# Main.net
KiCad netlist of a schematic drawn in Altium Designer
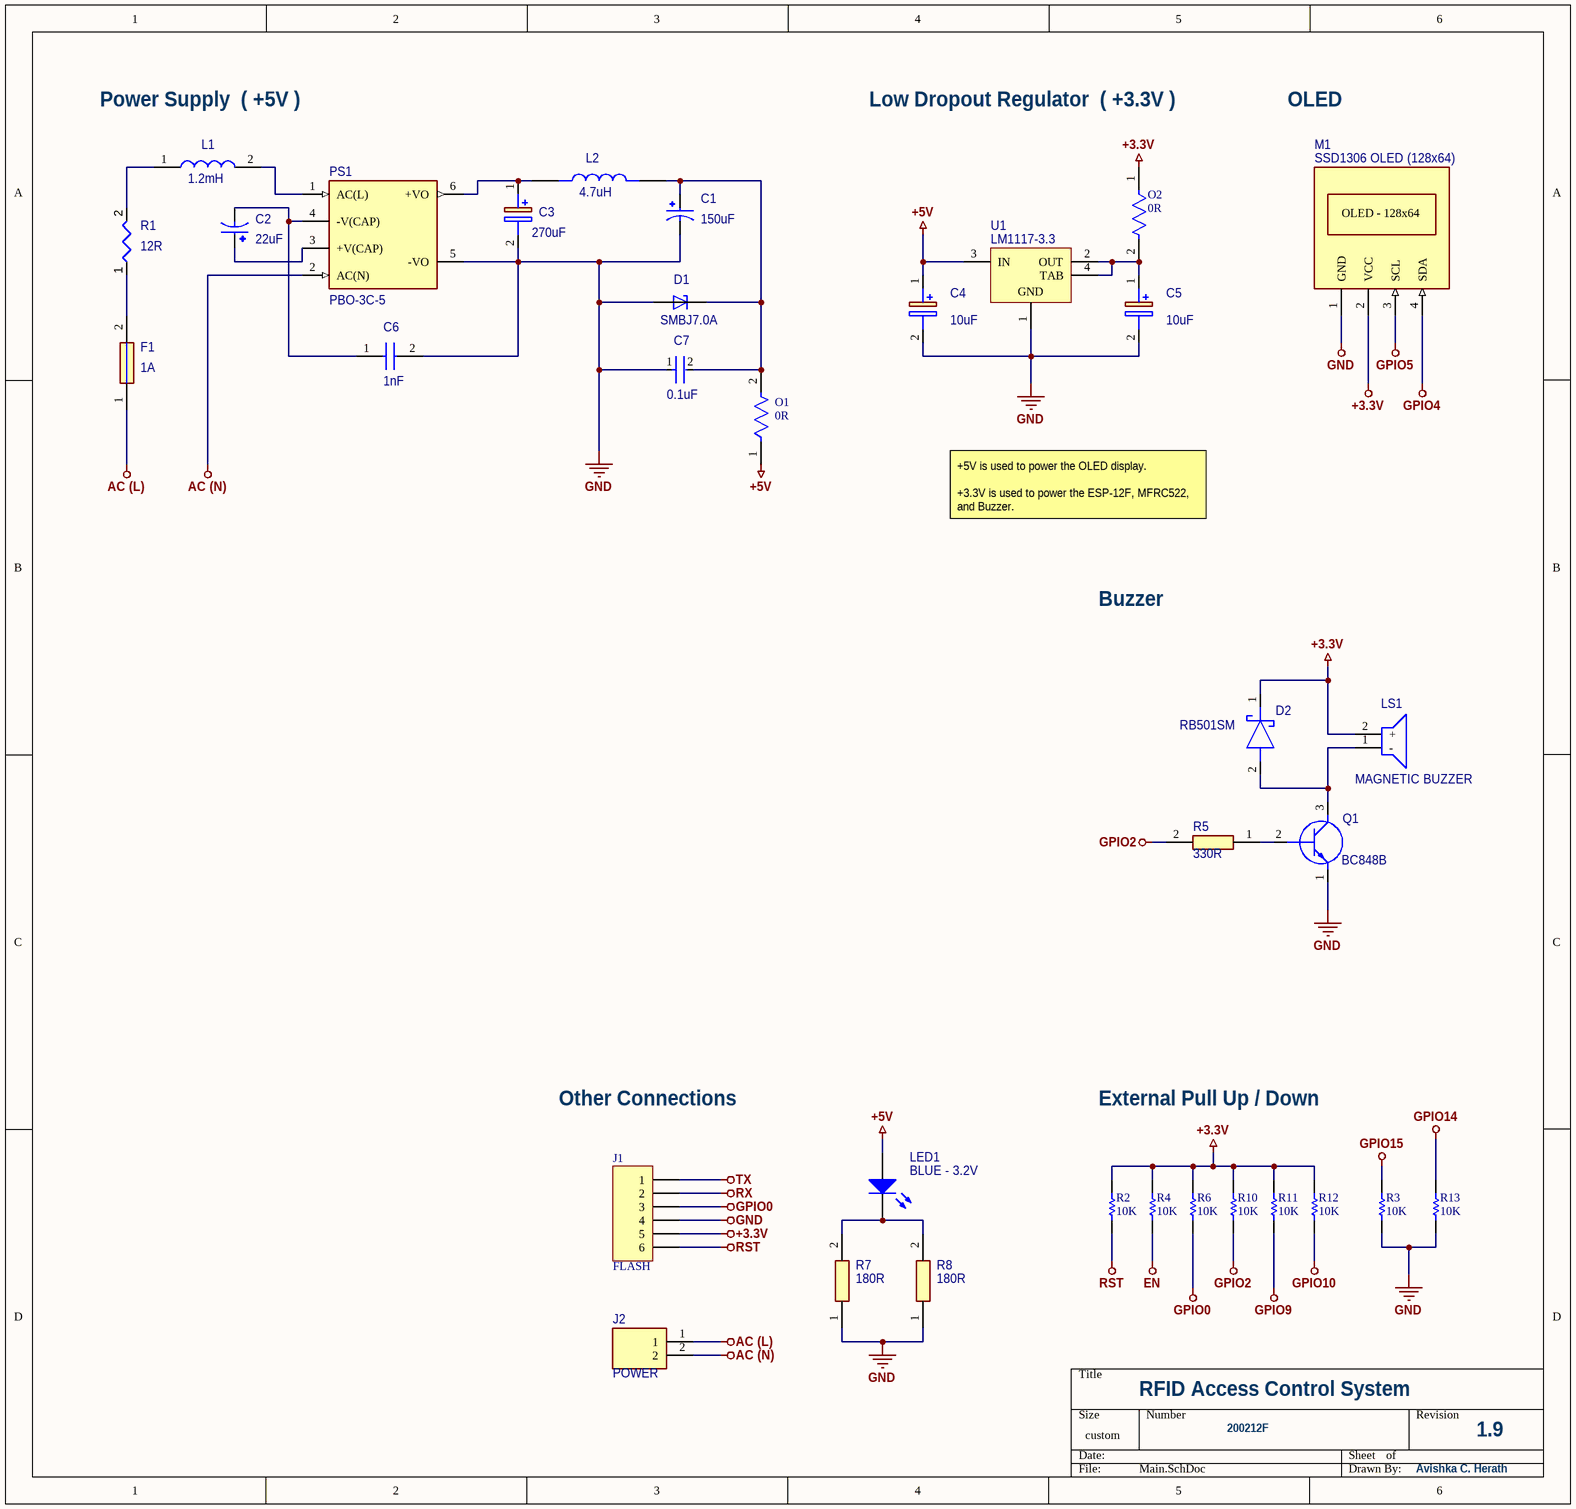
[diagram p0: Main.SchDoc]

(export (version "E")
  (design (tool "Eeschema 10.0.6"))
  (components
    (comp (ref "C1")
      (value "150uF")
      (footprint "CAPPRD500W60D800H1150")
      (description "FR-A")
      (fields (field (name "MF") "{'manufacturer': u'Panasonic'}") (field (name "MP") "UHE1V151MPD1TD"))
      (libsource (lib "SnapEDA_Library") (part "EEUFR1V221B"))
    )
    (comp (ref "C2")
      (value "22uF")
      (footprint "CAPPRD750W80D1600H2500")
      (description "Aluminum Electrolytic Capacitors - Radial Leaded")
      (fields (field (name "MF") "Nichicon") (field (name "MP") "UVR2W220MHD"))
      (libsource (lib "SnapEDA_Library") (part "EEUTP1E272B"))
    )
    (comp (ref "C3")
      (value "270uF")
      (footprint "CAPPRD250W65D630H900")
      (description "Aluminum Organic Polymer Capacitors")
      (fields
        (field (name "MANUFACTURER_PART_NUMBER") "A750EM277M1CAAE015")
        (field (name "MOUSER PART NUMBER") "667-6SEPC560MW+TSS")
      )
      (libsource (lib "SamacSys") (part "6SEPC560MW+TSS"))
    )
    (comp (ref "C4")
      (value "10uF")
      (footprint "SamacSys:T491B")
      (description "Capacitor Polarised")
      (fields
        (field (name "MANUFACTURER_PART_NUMBER") "T491B106M010AT")
        (field (name "MOUSER PART NUMBER") "80-T491B106M010")
      )
      (libsource (lib "*") (part "T491B106M010AT"))
    )
    (comp (ref "C5")
      (value "10uF")
      (footprint "SamacSys:T491B")
      (description "Capacitor Polarised")
      (fields
        (field (name "MANUFACTURER_PART_NUMBER") "T491B106M010AT")
        (field (name "MOUSER PART NUMBER") "80-T491B106M010")
      )
      (libsource (lib "*") (part "T491B106M010AT"))
    )
    (comp (ref "C6")
      (value "1nF")
      (footprint "SamacSys:B32529C8102J")
      (description "Capacitor")
      (fields
        (field (name "MANUFACTURER_PART_NUMBER") "B32529C8102J")
        (field (name "MOUSER PART NUMBER") "871-B32529C8102J")
      )
      (libsource (lib "*") (part "B32529C8102J"))
    )
    (comp (ref "C7")
      (value "0.1uF")
      (footprint "FP-CL10-0_1-MFG")
      (description "CAP CER 0.1UF 50V X7R 0603")
      (fields
        (field (name "MANUFACTURER") "Samsung Electro-Mechanics America, Inc")
        (field (name "MANUFACTURER PART NUMBER") "CL10B104JB8NNNC")
      )
      (libsource (lib "Altium Content Vault") (part "b4654b650e69147ec39a6b967a45e02"))
    )
    (comp (ref "D1")
      (value "SMBJ7.0A")
      (footprint "DIOM4336X265N")
      (fields (field (name "MF") "{'manufacturer': u'Littelfuse'}"))
      (libsource (lib "SnapEDA_Library") (part "SMBJ7.0A"))
    )
    (comp (ref "D2")
      (value "RB501SM")
      (footprint "SamacSys:RB501SM30FHT2R")
      (description "Schottky Diode")
      (fields
        (field (name "MANUFACTURER_PART_NUMBER") "RB501SM-30FHT2R")
        (field (name "MOUSER PART NUMBER") "755-RB501SM-30FHT2R")
      )
      (libsource (lib "*") (part "RB501SM-30FHT2R"))
    )
    (comp (ref "F1")
      (value "1A")
      (footprint "SS5H1AAPH")
      (description "Fuse")
      (fields
        (field (name "MOUSER PART NUMBER") "504-SS-5H-1A-APH")
        (field (name "MANUFACTURER_PART_NUMBER") "SS-5H-1A-APH")
      )
      (libsource (lib "University of Moratuwa") (part "SS-5H-1A-APH"))
    )
    (comp (ref "J1")
      (value "FLASH")
      (footprint "My_1X06")
      (description "Header, 6-Pin")
      (fields (field (name "ASID PART NUMBER") "Header 6-AS"))
      (libsource (lib "Mylib+Rev+4") (part "Header 6"))
    )
    (comp (ref "J2")
      (value "POWER")
      (footprint "SamacSys:TB00250002BE")
      (description "Connector")
      (fields
        (field (name "MANUFACTURER_PART_NUMBER") "TB002-500-02BE")
        (field (name "MOUSER PART NUMBER") "490-TB002-500-02BE")
      )
      (libsource (lib "*") (part "TB002-500-02BE"))
    )
    (comp (ref "L1")
      (value "1.2mH")
      (footprint "SamacSys:RLB9012122KL")
      (description "Inductor")
      (fields
        (field (name "MANUFACTURER_PART_NUMBER") "RLB9012-122KL")
        (field (name "MOUSER PART NUMBER") "652-RLB9012-122KL")
      )
      (libsource (lib "*") (part "RLB9012-122KL"))
    )
    (comp (ref "L2")
      (value "4.7uH")
      (footprint "IND_ASPI-0615FS-4R7M-T2")
      (fields (field (name "MF") "{'manufacturer': u'Abracon'}") (field (name "MP") "ASPI-0615FS-4R7M-T2"))
      (libsource (lib "SnapEDA_Library") (part "ASPI-0615FS-4R7M-T2"))
    )
    (comp (ref "LED1")
      (value "BLUE - 3.2V")
      (footprint "3528")
      (description "SMD mono-color Top LED, WL-SMTW, Blue")
      (fields (field (name "PARTNUMBER") "150141BS73100") (field (name "MANUFACTURER") "Wuerth Elektronik"))
      (libsource (lib "Altium Content Vault") (part "WE-LED_K1A2-2"))
    )
    (comp (ref "LS1")
      (value "MAGNETIC BUZZER")
      (footprint "SamacSys:CMI1295IC0385T")
      (description "Loudspeaker or Buzzer")
      (fields
        (field (name "MANUFACTURER_PART_NUMBER") "CMI-1295IC-0385T")
        (field (name "MOUSER PART NUMBER") "490-CMI-1295IC-0385T")
      )
      (libsource (lib "*") (part "CMI-1295IC-0385T"))
    )
    (comp (ref "M1")
      (value "SSD1306 OLED (128x64)")
      (footprint "SSD1306 OLED (128x64)-Footprint-1")
      (libsource (lib "University of Moratuwa") (part "SSD1306 OLED (128x64)"))
    )
    (comp (ref "O1")
      (value "0R")
      (footprint "FP-RC0805-MFG")
      (description "RES SMD 0 OHM JUMPER 1/8W 0805")
      (fields
        (field (name "OCTOPART") "https://octopart.com/rc0805fr-070rl-yageo-9293404")
        (field (name "MANUFACTURER") "Yageo")
      )
      (libsource (lib "Altium Content Vault") (part "1029c3af85768c4190bb7ad29bc67b5"))
    )
    (comp (ref "O2")
      (value "0R")
      (footprint "FP-RC0805-MFG")
      (description "RES SMD 0 OHM JUMPER 1/8W 0805")
      (fields
        (field (name "OCTOPART") "https://octopart.com/rc0805fr-070rl-yageo-9293404")
        (field (name "MANUFACTURER") "Yageo")
      )
      (libsource (lib "Altium Content Vault") (part "1029c3af85768c4190bb7ad29bc67b5"))
    )
    (comp (ref "PS1")
      (value "PBO-3C-5")
      (footprint "CONV_PBO-3C-5")
      (fields (field (name "MF") "{'manufacturer': u'CUI'}"))
      (libsource (lib "SnapEDA_Library") (part "PBO-3C-5"))
    )
    (comp (ref "Q1")
      (value "BC848B")
      (footprint "SamacSys:SOT95P240X120-3N")
      (description "Transistor BJT NPN")
      (fields
        (field (name "MANUFACTURER_PART_NUMBER") "BC848BHZGT116")
        (field (name "MOUSER PART NUMBER") "755-BC848BHZGT116")
      )
      (libsource (lib "*") (part "BC848BHZGT116"))
    )
    (comp (ref "R1")
      (value "12R")
      (footprint "WA84-12RJI-Footprint-1")
      (libsource (lib "University of Moratuwa") (part "WA84-12RJI"))
    )
    (comp (ref "R2")
      (value "10K")
      (footprint "RESC2013X60X35ML10T20")
      (description "Res Thick Film 0805 10K Ohm 1% 0.125W(1/8W) +/-100ppm/C Epoxy Pad SMD T/R")
      (libsource (lib "University of Moratuwa") (part "RES-2"))
    )
    (comp (ref "R3")
      (value "10K")
      (footprint "RESC2013X60X35ML10T20")
      (description "Res Thick Film 0805 10K Ohm 1% 0.125W(1/8W) +/-100ppm/C Epoxy Pad SMD T/R")
      (libsource (lib "University of Moratuwa") (part "RES-2"))
    )
    (comp (ref "R4")
      (value "10K")
      (footprint "RESC2013X60X35ML10T20")
      (description "Res Thick Film 0805 10K Ohm 1% 0.125W(1/8W) +/-100ppm/C Epoxy Pad SMD T/R")
      (libsource (lib "University of Moratuwa") (part "RES-2"))
    )
    (comp (ref "R5")
      (value "330R")
      (footprint "SamacSys:RESC2012X60N")
      (description "Resistor")
      (fields
        (field (name "MANUFACTURER_PART_NUMBER") "RC0805FR-07330RL")
        (field (name "MOUSER PART NUMBER") "603-RC0805FR-07330RL")
      )
      (libsource (lib "*") (part "RC0805FR-07330RL"))
    )
    (comp (ref "R6")
      (value "10K")
      (footprint "RESC2013X60X35ML10T20")
      (description "Res Thick Film 0805 10K Ohm 1% 0.125W(1/8W) +/-100ppm/C Epoxy Pad SMD T/R")
      (libsource (lib "University of Moratuwa") (part "RES-2"))
    )
    (comp (ref "R7")
      (value "180R")
      (footprint "SamacSys:RESC2012X60N")
      (description "Resistor")
      (fields
        (field (name "MANUFACTURER_PART_NUMBER") "RC0805FR-07180RL")
        (field (name "MOUSER PART NUMBER") "603-RC0805FR-07180RL")
      )
      (libsource (lib "*") (part "RC0805FR-07180RL"))
    )
    (comp (ref "R8")
      (value "180R")
      (footprint "SamacSys:RESC2012X60N")
      (description "Resistor")
      (fields
        (field (name "MANUFACTURER_PART_NUMBER") "RC0805FR-07180RL")
        (field (name "MOUSER PART NUMBER") "603-RC0805FR-07180RL")
      )
      (libsource (lib "*") (part "RC0805FR-07180RL"))
    )
    (comp (ref "R10")
      (value "10K")
      (footprint "RESC2013X60X35ML10T20")
      (description "Res Thick Film 0805 10K Ohm 1% 0.125W(1/8W) +/-100ppm/C Epoxy Pad SMD T/R")
      (libsource (lib "University of Moratuwa") (part "RES-2"))
    )
    (comp (ref "R11")
      (value "10K")
      (footprint "RESC2013X60X35ML10T20")
      (description "Res Thick Film 0805 10K Ohm 1% 0.125W(1/8W) +/-100ppm/C Epoxy Pad SMD T/R")
      (libsource (lib "University of Moratuwa") (part "RES-2"))
    )
    (comp (ref "R12")
      (value "10K")
      (footprint "RESC2013X60X35ML10T20")
      (description "Res Thick Film 0805 10K Ohm 1% 0.125W(1/8W) +/-100ppm/C Epoxy Pad SMD T/R")
      (libsource (lib "University of Moratuwa") (part "RES-2"))
    )
    (comp (ref "R13")
      (value "10K")
      (footprint "RESC2013X60X35ML10T20")
      (description "Res Thick Film 0805 10K Ohm 1% 0.125W(1/8W) +/-100ppm/C Epoxy Pad SMD T/R")
      (libsource (lib "University of Moratuwa") (part "RES-2"))
    )
    (comp (ref "U1")
      (value "LM1117-3.3")
      (footprint "DCY0004A_L")
      (description "800mA Low-Dropout Linear Regulator, 4-pin SOT-223, Pb-Free")
      (fields
        (field (name "PARTNUMBER") "LM1117MPX-3.3/NOPB")
        (field (name "MANUFACTURER") "Texas Instruments")
      )
      (libsource (lib "Altium Content Vault") (part "PM-REG-LM1086-SOT4"))
    )
  )
  (nets
    (net (code "1") (name "+3.3V") (class "Default")
      (node (ref "D2") (pin "1") (pinfunction "K_1") (pintype "passive"))
      (node (ref "J1") (pin "5") (pinfunction "5_5") (pintype "passive"))
      (node (ref "LS1") (pin "2") (pinfunction "+_2") (pintype "passive"))
      (node (ref "M1") (pin "2") (pinfunction "VCC_2") (pintype "power_in"))
      (node (ref "O2") (pin "1") (pinfunction "1_1") (pintype "passive"))
      (node (ref "R10") (pin "2") (pinfunction "2_2") (pintype "passive"))
      (node (ref "R11") (pin "2") (pinfunction "2_2") (pintype "passive"))
      (node (ref "R12") (pin "2") (pinfunction "2_2") (pintype "passive"))
      (node (ref "R2") (pin "1") (pinfunction "1_1") (pintype "passive"))
      (node (ref "R4") (pin "1") (pinfunction "1_1") (pintype "passive"))
      (node (ref "R6") (pin "2") (pinfunction "2_2") (pintype "passive"))
    )
    (net (code "2") (name "+5V") (class "Default")
      (node (ref "C4") (pin "1") (pinfunction "+_1") (pintype "passive"))
      (node (ref "LED1") (pin "2") (pinfunction "A_2") (pintype "passive"))
      (node (ref "O1") (pin "1") (pinfunction "1_1") (pintype "passive"))
      (node (ref "U1") (pin "3") (pinfunction "IN_3") (pintype "power_in"))
    )
    (net (code "3") (name "AC (L)") (class "Default")
      (node (ref "F1") (pin "1") (pinfunction "1_1") (pintype "passive"))
      (node (ref "J2") (pin "1") (pinfunction "1_1") (pintype "passive"))
    )
    (net (code "4") (name "AC (N)") (class "Default")
      (node (ref "J2") (pin "2") (pinfunction "2_2") (pintype "passive"))
      (node (ref "PS1") (pin "2") (pinfunction "AC(N)_2") (pintype "input"))
    )
    (net (code "5") (name "EN") (class "Default")
      (node (ref "R4") (pin "2") (pinfunction "2_2") (pintype "passive"))
    )
    (net (code "6") (name "GND") (class "Default")
      (node (ref "C1") (pin "N") (pinfunction "N_N") (pintype "passive"))
      (node (ref "C3") (pin "2") (pinfunction "-_2") (pintype "passive"))
      (node (ref "C4") (pin "2") (pinfunction "-_2") (pintype "passive"))
      (node (ref "C5") (pin "2") (pinfunction "-_2") (pintype "passive"))
      (node (ref "C6") (pin "2") (pinfunction "2_2") (pintype "passive"))
      (node (ref "C7") (pin "1") (pinfunction "1_1") (pintype "passive"))
      (node (ref "D1") (pin "A") (pinfunction "A_A") (pintype "passive"))
      (node (ref "J1") (pin "4") (pinfunction "4_4") (pintype "passive"))
      (node (ref "M1") (pin "1") (pinfunction "GND_1") (pintype "power_in"))
      (node (ref "PS1") (pin "5") (pinfunction "-VO_5") (pintype "passive"))
      (node (ref "Q1") (pin "1") (pinfunction "E_1") (pintype "passive"))
      (node (ref "R13") (pin "2") (pinfunction "2_2") (pintype "passive"))
      (node (ref "R3") (pin "2") (pinfunction "2_2") (pintype "passive"))
      (node (ref "R7") (pin "1") (pinfunction "1_1") (pintype "passive"))
      (node (ref "R8") (pin "1") (pinfunction "1_1") (pintype "passive"))
      (node (ref "U1") (pin "1") (pinfunction "GND_1") (pintype "power_in"))
    )
    (net (code "7") (name "GPIO0") (class "Default")
      (node (ref "J1") (pin "3") (pinfunction "3_3") (pintype "passive"))
      (node (ref "R6") (pin "1") (pinfunction "1_1") (pintype "passive"))
    )
    (net (code "8") (name "GPIO2") (class "Default")
      (node (ref "R10") (pin "1") (pinfunction "1_1") (pintype "passive"))
      (node (ref "R5") (pin "2") (pinfunction "2_2") (pintype "passive"))
    )
    (net (code "9") (name "GPIO4") (class "Default")
      (node (ref "M1") (pin "4") (pinfunction "SDA_4") (pintype "input"))
    )
    (net (code "10") (name "GPIO5") (class "Default")
      (node (ref "M1") (pin "3") (pinfunction "SCL_3") (pintype "input"))
    )
    (net (code "11") (name "GPIO9") (class "Default")
      (node (ref "R11") (pin "1") (pinfunction "1_1") (pintype "passive"))
    )
    (net (code "12") (name "GPIO10") (class "Default")
      (node (ref "R12") (pin "1") (pinfunction "1_1") (pintype "passive"))
    )
    (net (code "13") (name "GPIO14") (class "Default")
      (node (ref "R13") (pin "1") (pinfunction "1_1") (pintype "passive"))
    )
    (net (code "14") (name "GPIO15") (class "Default")
      (node (ref "R3") (pin "1") (pinfunction "1_1") (pintype "passive"))
    )
    (net (code "15") (name "Net-(C1-PadP)") (class "Default")
      (node (ref "C1") (pin "P") (pinfunction "P_P") (pintype "passive"))
      (node (ref "C7") (pin "2") (pinfunction "2_2") (pintype "passive"))
      (node (ref "D1") (pin "C") (pinfunction "C_C") (pintype "passive"))
      (node (ref "L2") (pin "2") (pinfunction "2_2") (pintype "passive"))
      (node (ref "O1") (pin "2") (pinfunction "2_2") (pintype "passive"))
    )
    (net (code "16") (name "Net-(C2-PadN)") (class "Default")
      (node (ref "C2") (pin "N") (pinfunction "N_N") (pintype "passive"))
      (node (ref "C6") (pin "1") (pinfunction "1_1") (pintype "passive"))
      (node (ref "PS1") (pin "4") (pinfunction "-V(CAP)_4") (pintype "passive"))
    )
    (net (code "17") (name "Net-(C3-+)") (class "Default")
      (node (ref "C3") (pin "1") (pinfunction "+_1") (pintype "passive"))
      (node (ref "L2") (pin "1") (pinfunction "1_1") (pintype "passive"))
      (node (ref "PS1") (pin "6") (pinfunction "+VO_6") (pintype "output"))
    )
    (net (code "18") (name "Net-(C5-+)") (class "Default")
      (node (ref "C5") (pin "1") (pinfunction "+_1") (pintype "passive"))
      (node (ref "O2") (pin "2") (pinfunction "2_2") (pintype "passive"))
      (node (ref "U1") (pin "2") (pinfunction "OUT_2") (pintype "power_in"))
      (node (ref "U1") (pin "4") (pinfunction "TAB_4") (pintype "power_in"))
    )
    (net (code "19") (name "Net-(D2-A)") (class "Default")
      (node (ref "D2") (pin "2") (pinfunction "A_2") (pintype "passive"))
      (node (ref "LS1") (pin "1") (pinfunction "-_1") (pintype "passive"))
      (node (ref "Q1") (pin "3") (pinfunction "C_3") (pintype "passive"))
    )
    (net (code "20") (name "Net-(F1-Pad2)") (class "Default")
      (node (ref "F1") (pin "2") (pinfunction "2_2") (pintype "passive"))
      (node (ref "R1") (pin "1") (pinfunction "1_1") (pintype "passive"))
    )
    (net (code "21") (name "Net-(L1-Pad1)") (class "Default")
      (node (ref "L1") (pin "1") (pinfunction "1_1") (pintype "passive"))
      (node (ref "R1") (pin "2") (pinfunction "2_2") (pintype "passive"))
    )
    (net (code "22") (name "Net-(LED1-K)") (class "Default")
      (node (ref "LED1") (pin "1") (pinfunction "K_1") (pintype "passive"))
      (node (ref "R7") (pin "2") (pinfunction "2_2") (pintype "passive"))
      (node (ref "R8") (pin "2") (pinfunction "2_2") (pintype "passive"))
    )
    (net (code "23") (name "Net-(PS1-+V(CAP))") (class "Default")
      (node (ref "C2") (pin "P") (pinfunction "P_P") (pintype "passive"))
      (node (ref "PS1") (pin "3") (pinfunction "+V(CAP)_3") (pintype "passive"))
    )
    (net (code "24") (name "Net-(PS1-AC(L))") (class "Default")
      (node (ref "L1") (pin "2") (pinfunction "2_2") (pintype "passive"))
      (node (ref "PS1") (pin "1") (pinfunction "AC(L)_1") (pintype "input"))
    )
    (net (code "25") (name "Net-(Q1-B)") (class "Default")
      (node (ref "Q1") (pin "2") (pinfunction "B_2") (pintype "passive"))
      (node (ref "R5") (pin "1") (pinfunction "1_1") (pintype "passive"))
    )
    (net (code "26") (name "RST") (class "Default")
      (node (ref "J1") (pin "6") (pinfunction "6_6") (pintype "passive"))
      (node (ref "R2") (pin "2") (pinfunction "2_2") (pintype "passive"))
    )
    (net (code "27") (name "RX") (class "Default")
      (node (ref "J1") (pin "2") (pinfunction "2_2") (pintype "passive"))
    )
    (net (code "28") (name "TX") (class "Default")
      (node (ref "J1") (pin "1") (pinfunction "1_1") (pintype "passive"))
    )
    (net (code "29") (name "unconnected-(PS1--V(CAP)-Pad4_2)") (class "Default")
      (node (ref "PS1") (pin "4_2") (pinfunction "-V(CAP)_4_2") (pintype "passive"))
    )
    (net (code "30") (name "unconnected-(PS1--VO-Pad5_2)") (class "Default")
      (node (ref "PS1") (pin "5_2") (pinfunction "-VO_5_2") (pintype "output"))
    )
  )
)
